# design_cty.net
KiCad netlist of a schematic drawn in Altium Designer
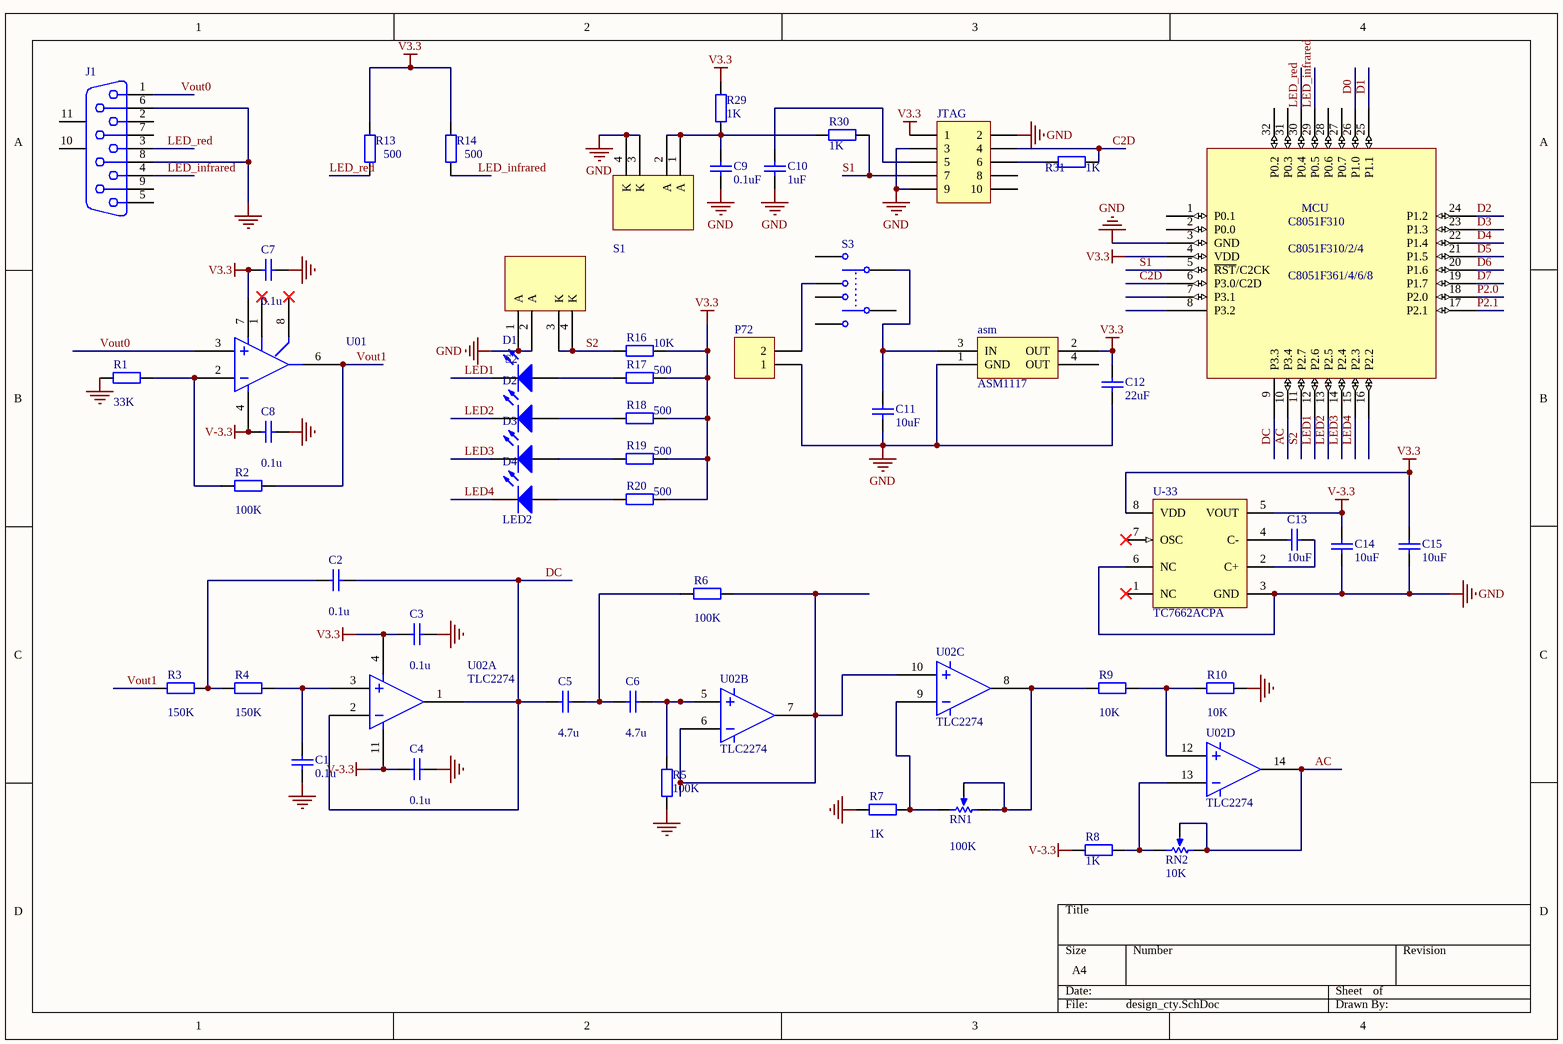
[diagram p0: design_cty.SchDoc]

(export (version "E")
  (design (tool "Eeschema 10.0.6"))
  (components
    (comp (ref "asm")
      (value "ASM1117")
      (footprint "SOT-223")
      (description "3.3V稳压芯片")
      (libsource (lib "fszhang") (part "ASM1117"))
    )
    (comp (ref "C1")
      (value "0.1u")
      (footprint "0805")
      (description "Capacitor")
      (fields (field (name "Comment") "Cap") (field (name "PUBLISHER") "Altium Limited"))
      (libsource (lib "Miscellaneous Devices") (part "Cap"))
    )
    (comp (ref "C2")
      (value "0.1u")
      (footprint "0805")
      (description "Capacitor")
      (fields (field (name "Comment") "Cap") (field (name "PUBLISHER") "Altium Limited"))
      (libsource (lib "Miscellaneous Devices") (part "Cap"))
    )
    (comp (ref "C3")
      (value "0.1u")
      (footprint "0805")
      (description "Capacitor")
      (fields (field (name "Comment") "Cap") (field (name "PUBLISHER") "Altium Limited"))
      (libsource (lib "Miscellaneous Devices") (part "Cap"))
    )
    (comp (ref "C4")
      (value "0.1u")
      (footprint "0805")
      (description "Capacitor")
      (fields (field (name "Comment") "Cap") (field (name "PUBLISHER") "Altium Limited"))
      (libsource (lib "Miscellaneous Devices") (part "Cap"))
    )
    (comp (ref "C5")
      (value "4.7u")
      (footprint "0805")
      (description "Capacitor")
      (fields (field (name "Comment") "Cap") (field (name "PUBLISHER") "Altium Limited"))
      (libsource (lib "Miscellaneous Devices") (part "Cap"))
    )
    (comp (ref "C6")
      (value "4.7u")
      (footprint "0805")
      (description "Capacitor")
      (fields (field (name "Comment") "Cap") (field (name "PUBLISHER") "Altium Limited"))
      (libsource (lib "Miscellaneous Devices") (part "Cap"))
    )
    (comp (ref "C7")
      (value "0.1u")
      (footprint "0805")
      (description "Capacitor")
      (fields (field (name "Comment") "Cap") (field (name "PUBLISHER") "Altium Limited"))
      (libsource (lib "Miscellaneous Devices") (part "Cap"))
    )
    (comp (ref "C8")
      (value "0.1u")
      (footprint "0805")
      (description "Capacitor")
      (fields (field (name "Comment") "Cap") (field (name "PUBLISHER") "Altium Limited"))
      (libsource (lib "Miscellaneous Devices") (part "Cap"))
    )
    (comp (ref "C9")
      (value "0.1uF")
      (footprint "0805")
      (description "Capacitor")
      (fields (field (name "Comment") "Cap") (field (name "PUBLISHER") "Altium Limited"))
      (libsource (lib "Miscellaneous Devices") (part "Cap"))
    )
    (comp (ref "C10")
      (value "1uF")
      (footprint "0805")
      (description "Capacitor")
      (fields (field (name "Comment") "Cap") (field (name "PUBLISHER") "Altium Limited"))
      (libsource (lib "Miscellaneous Devices") (part "Cap"))
    )
    (comp (ref "C11")
      (value "10uF")
      (footprint "1206")
      (description "Capacitor")
      (fields (field (name "Comment") "Cap") (field (name "PUBLISHER") "Altium Limited"))
      (libsource (lib "Miscellaneous Devices") (part "Cap"))
    )
    (comp (ref "C12")
      (value "22uF")
      (footprint "1206")
      (description "Capacitor")
      (fields (field (name "Comment") "Cap") (field (name "PUBLISHER") "Altium Limited"))
      (libsource (lib "Miscellaneous Devices") (part "Cap"))
    )
    (comp (ref "C13")
      (value "10uF")
      (footprint "1206")
      (description "Capacitor")
      (fields (field (name "Comment") "Cap") (field (name "PUBLISHER") "Altium Limited"))
      (libsource (lib "Miscellaneous Devices") (part "Cap"))
    )
    (comp (ref "C14")
      (value "10uF")
      (footprint "1206")
      (description "Capacitor")
      (fields (field (name "Comment") "Cap") (field (name "PUBLISHER") "Altium Limited"))
      (libsource (lib "Miscellaneous Devices") (part "Cap"))
    )
    (comp (ref "C15")
      (value "10uF")
      (footprint "1206")
      (description "Capacitor")
      (fields (field (name "Comment") "Cap") (field (name "PUBLISHER") "Altium Limited"))
      (libsource (lib "Miscellaneous Devices") (part "Cap"))
    )
    (comp (ref "D1")
      (value "LED2")
      (footprint "0805")
      (description "Typical RED, GREEN, YELLOW, AMBER GaAs LED")
      (fields (field (name "PUBLISHER") "Altium Limited"))
      (libsource (lib "Miscellaneous Devices") (part "LED2"))
    )
    (comp (ref "D2")
      (value "LED2")
      (footprint "0805")
      (description "Typical RED, GREEN, YELLOW, AMBER GaAs LED")
      (fields (field (name "PUBLISHER") "Altium Limited"))
      (libsource (lib "Miscellaneous Devices") (part "LED2"))
    )
    (comp (ref "D3")
      (value "LED2")
      (footprint "0805")
      (description "Typical RED, GREEN, YELLOW, AMBER GaAs LED")
      (fields (field (name "PUBLISHER") "Altium Limited"))
      (libsource (lib "Miscellaneous Devices") (part "LED2"))
    )
    (comp (ref "D4")
      (value "LED2")
      (footprint "0805")
      (description "Typical RED, GREEN, YELLOW, AMBER GaAs LED")
      (fields (field (name "PUBLISHER") "Altium Limited"))
      (libsource (lib "Miscellaneous Devices") (part "LED2"))
    )
    (comp (ref "J1")
      (value "D Connector 9")
      (footprint "DSUB1.385-2H9")
      (description "Receptacle Assembly, 9 Position, Right Angle")
      (fields (field (name "PUBLISHER") "Altium Limited"))
      (libsource (lib "Miscellaneous Connectors") (part "D Connector 9"))
    )
    (comp (ref "JTAG")
      (value "Header 5X2")
      (footprint "HDR2X5")
      (description "Header, 5-Pin, Dual row")
      (fields (field (name "PUBLISHER") "Altium Limited"))
      (libsource (lib "Miscellaneous Connectors") (part "Header 5X2"))
    )
    (comp (ref "MCU")
      (value "C8051F310")
      (footprint "LQFP-32")
      (libsource (lib "Siliconsch") (part "C8051F310/2/4_361/4/6/8"))
    )
    (comp (ref "P72")
      (value "Header 2")
      (footprint "HDR1X2")
      (description "Header, 2-Pin")
      (fields (field (name "PUBLISHER") "Altium Limited"))
      (libsource (lib "Miscellaneous Connectors") (part "Header 2"))
    )
    (comp (ref "R1")
      (value "33K")
      (footprint "0805")
      (description "Resistor")
      (fields (field (name "Comment") "Res2") (field (name "PUBLISHER") "Altium Limited"))
      (libsource (lib "") (part "Res2_1"))
    )
    (comp (ref "R2")
      (value "100K")
      (footprint "0805")
      (description "Resistor")
      (fields (field (name "Comment") "Res2") (field (name "PUBLISHER") "Altium Limited"))
      (libsource (lib "") (part "Res2_1"))
    )
    (comp (ref "R3")
      (value "150K")
      (footprint "0805")
      (description "Resistor")
      (fields (field (name "Comment") "Res2") (field (name "PUBLISHER") "Altium Limited"))
      (libsource (lib "") (part "Res2_1"))
    )
    (comp (ref "R4")
      (value "150K")
      (footprint "0805")
      (description "Resistor")
      (fields (field (name "Comment") "Res2") (field (name "PUBLISHER") "Altium Limited"))
      (libsource (lib "") (part "Res2_1"))
    )
    (comp (ref "R5")
      (value "100K")
      (footprint "0805")
      (description "Resistor")
      (fields (field (name "Comment") "Res2") (field (name "PUBLISHER") "Altium Limited"))
      (libsource (lib "Miscellaneous Devices") (part "Res2"))
    )
    (comp (ref "R6")
      (value "100K")
      (footprint "0805")
      (description "Resistor")
      (fields (field (name "Comment") "Res2") (field (name "PUBLISHER") "Altium Limited"))
      (libsource (lib "") (part "Res2_1"))
    )
    (comp (ref "R7")
      (value "1K")
      (footprint "0805")
      (description "Resistor")
      (fields (field (name "Comment") "Res2") (field (name "PUBLISHER") "Altium Limited"))
      (libsource (lib "") (part "Res2_1"))
    )
    (comp (ref "R8")
      (value "1K")
      (footprint "0805")
      (description "Resistor")
      (fields (field (name "Comment") "Res2") (field (name "PUBLISHER") "Altium Limited"))
      (libsource (lib "") (part "Res2_2"))
    )
    (comp (ref "R9")
      (value "10K")
      (footprint "0805")
      (description "Resistor")
      (fields (field (name "Comment") "Res2") (field (name "PUBLISHER") "Altium Limited"))
      (libsource (lib "") (part "Res2_1"))
    )
    (comp (ref "R10")
      (value "10K")
      (footprint "0805")
      (description "Resistor")
      (fields (field (name "Comment") "Res2") (field (name "PUBLISHER") "Altium Limited"))
      (libsource (lib "") (part "Res2_1"))
    )
    (comp (ref "R13")
      (value "500")
      (footprint "0805")
      (description "Resistor")
      (fields (field (name "Comment") "Res2") (field (name "PUBLISHER") "Altium Limited"))
      (libsource (lib "Miscellaneous Devices") (part "Res2"))
    )
    (comp (ref "R14")
      (value "500")
      (footprint "0805")
      (description "Resistor")
      (fields (field (name "Comment") "Res2") (field (name "PUBLISHER") "Altium Limited"))
      (libsource (lib "Miscellaneous Devices") (part "Res2"))
    )
    (comp (ref "R16")
      (value "10K")
      (footprint "0805")
      (description "Resistor")
      (fields (field (name "Comment") "Res2") (field (name "PUBLISHER") "Altium Limited"))
      (libsource (lib "") (part "Res2_1"))
    )
    (comp (ref "R17")
      (value "500")
      (footprint "0805")
      (description "Resistor")
      (fields (field (name "Comment") "Res2") (field (name "PUBLISHER") "Altium Limited"))
      (libsource (lib "") (part "Res2_1"))
    )
    (comp (ref "R18")
      (value "500")
      (footprint "0805")
      (description "Resistor")
      (fields (field (name "Comment") "Res2") (field (name "PUBLISHER") "Altium Limited"))
      (libsource (lib "") (part "Res2_1"))
    )
    (comp (ref "R19")
      (value "500")
      (footprint "0805")
      (description "Resistor")
      (fields (field (name "Comment") "Res2") (field (name "PUBLISHER") "Altium Limited"))
      (libsource (lib "") (part "Res2_1"))
    )
    (comp (ref "R20")
      (value "500")
      (footprint "0805")
      (description "Resistor")
      (fields (field (name "Comment") "Res2") (field (name "PUBLISHER") "Altium Limited"))
      (libsource (lib "") (part "Res2_1"))
    )
    (comp (ref "R29")
      (value "1K")
      (footprint "0805")
      (description "Resistor")
      (fields (field (name "Comment") "Res2") (field (name "PUBLISHER") "Altium Limited"))
      (libsource (lib "Miscellaneous Devices") (part "Res2"))
    )
    (comp (ref "R30")
      (value "1K")
      (footprint "0805")
      (description "Resistor")
      (fields (field (name "Comment") "Res2") (field (name "PUBLISHER") "Altium Limited"))
      (libsource (lib "") (part "Res2_1"))
    )
    (comp (ref "R31")
      (value "1K")
      (footprint "0805")
      (description "Resistor")
      (fields (field (name "Comment") "Res2") (field (name "PUBLISHER") "Altium Limited"))
      (libsource (lib "") (part "Res2_1"))
    )
    (comp (ref "RN1")
      (value "100K")
      (footprint "VR5")
      (description "Potentiometer")
      (fields (field (name "Comment") "RPot") (field (name "PUBLISHER") "Altium Limited"))
      (libsource (lib "Miscellaneous Devices") (part "RPot"))
    )
    (comp (ref "RN2")
      (value "10K")
      (footprint "VR5")
      (description "Potentiometer")
      (fields (field (name "Comment") "RPot") (field (name "PUBLISHER") "Altium Limited"))
      (libsource (lib "Miscellaneous Devices") (part "RPot"))
    )
    (comp (ref "S1") (value "K1") (footprint "KEY1") (libsource (lib "") (part "K1_1")))
    (comp (ref "S2") (value "K1") (footprint "KEY1") (libsource (lib "2012_2") (part "K1")))
    (comp (ref "S3")
      (value "SW-DPDT")
      (footprint "DPDT-6")
      (description "Double-Pole, Double-Throw Switch")
      (fields (field (name "PUBLISHER") "Altium Limited"))
      (libsource (lib "Miscellaneous Devices") (part "SW-DPDT"))
    )
    (comp (ref "U-33")
      (value "TC7662ACPA")
      (footprint "SO-8")
      (description "Super Charge Pump DC-to-DC Voltage Converter, 12kHz, 8-Pin PDIP, Commercial Temperature")
      (fields (field (name "PUBLISHER") "Altium Limited"))
      (libsource (lib "Microchip Power Mgt Charge Pump") (part "TC7662ACPA"))
    )
    (comp (ref "U01") (value "OP-07") (footprint "DIP-8") (libsource (lib "2012_1") (part "OP-07")))
    (comp (ref "U02") (value "TLC2274") (footprint "SOP-14N") (libsource (lib "2012_1") (part "LM324")))
  )
  (nets
    (net (code "1") (name "/AC") (class "Default")
      (node (ref "MCU") (pin "10") (pinfunction "P3.4_10") (pintype "bidirectional"))
      (node (ref "RN2") (pin "1") (pinfunction "TOP_1") (pintype "passive"))
      (node (ref "RN2") (pin "3") (pinfunction "TAP_3") (pintype "passive"))
      (node (ref "U02") (pin "14") (pintype "passive"))
    )
    (net (code "2") (name "/C2D") (class "Default")
      (node (ref "JTAG") (pin "4") (pinfunction "4_4") (pintype "passive"))
      (node (ref "MCU") (pin "6") (pinfunction "P3.0/C2D_6") (pintype "bidirectional"))
      (node (ref "R31") (pin "2") (pinfunction "2_2") (pintype "passive"))
    )
    (net (code "3") (name "/D0") (class "Default")
      (node (ref "MCU") (pin "26") (pinfunction "P1.0_26") (pintype "bidirectional"))
    )
    (net (code "4") (name "/D1") (class "Default")
      (node (ref "MCU") (pin "25") (pinfunction "P1.1_25") (pintype "bidirectional"))
    )
    (net (code "5") (name "/D2") (class "Default")
      (node (ref "MCU") (pin "24") (pinfunction "P1.2_24") (pintype "bidirectional"))
    )
    (net (code "6") (name "/D3") (class "Default")
      (node (ref "MCU") (pin "23") (pinfunction "P1.3_23") (pintype "bidirectional"))
    )
    (net (code "7") (name "/D4") (class "Default")
      (node (ref "MCU") (pin "22") (pinfunction "P1.4_22") (pintype "bidirectional"))
    )
    (net (code "8") (name "/D5") (class "Default")
      (node (ref "MCU") (pin "21") (pinfunction "P1.5_21") (pintype "bidirectional"))
    )
    (net (code "9") (name "/D6") (class "Default")
      (node (ref "MCU") (pin "20") (pinfunction "P1.6_20") (pintype "bidirectional"))
    )
    (net (code "10") (name "/D7") (class "Default")
      (node (ref "MCU") (pin "19") (pinfunction "P1.7_19") (pintype "bidirectional"))
    )
    (net (code "11") (name "/DC") (class "Default")
      (node (ref "C2") (pin "2") (pinfunction "2_2") (pintype "passive"))
      (node (ref "C5") (pin "1") (pinfunction "1_1") (pintype "passive"))
      (node (ref "MCU") (pin "9") (pinfunction "P3.3_9") (pintype "power_in"))
      (node (ref "U02") (pin "1") (pintype "passive"))
      (node (ref "U02") (pin "2") (pintype "passive"))
    )
    (net (code "12") (name "/LED1") (class "Default")
      (node (ref "D1") (pin "2") (pinfunction "K_2") (pintype "passive"))
      (node (ref "MCU") (pin "12") (pinfunction "P2.6_12") (pintype "bidirectional"))
    )
    (net (code "13") (name "/LED2") (class "Default")
      (node (ref "D2") (pin "2") (pinfunction "K_2") (pintype "passive"))
      (node (ref "MCU") (pin "13") (pinfunction "P2.5_13") (pintype "bidirectional"))
    )
    (net (code "14") (name "/LED3") (class "Default")
      (node (ref "D3") (pin "2") (pinfunction "K_2") (pintype "passive"))
      (node (ref "MCU") (pin "14") (pinfunction "P2.4_14") (pintype "bidirectional"))
    )
    (net (code "15") (name "/LED4") (class "Default")
      (node (ref "D4") (pin "2") (pinfunction "K_2") (pintype "passive"))
      (node (ref "MCU") (pin "15") (pinfunction "P2.3_15") (pintype "bidirectional"))
    )
    (net (code "16") (name "/LED_infrared") (class "Default")
      (node (ref "J1") (pin "4") (pinfunction "4_4") (pintype "passive"))
      (node (ref "MCU") (pin "29") (pinfunction "P0.5_29") (pintype "bidirectional"))
      (node (ref "R14") (pin "1") (pinfunction "1_1") (pintype "passive"))
    )
    (net (code "17") (name "/LED_red") (class "Default")
      (node (ref "J1") (pin "3") (pinfunction "3_3") (pintype "passive"))
      (node (ref "MCU") (pin "30") (pinfunction "P0.4_30") (pintype "bidirectional"))
      (node (ref "R13") (pin "1") (pinfunction "1_1") (pintype "passive"))
    )
    (net (code "18") (name "/P2.0") (class "Default")
      (node (ref "MCU") (pin "18") (pinfunction "P2.0_18") (pintype "bidirectional"))
    )
    (net (code "19") (name "/P2.1") (class "Default")
      (node (ref "MCU") (pin "17") (pinfunction "P2.1_17") (pintype "bidirectional"))
    )
    (net (code "20") (name "/S1") (class "Default")
      (node (ref "JTAG") (pin "7") (pinfunction "7_7") (pintype "passive"))
      (node (ref "MCU") (pin "5") (pinfunction "~{RST}/C2CK_5") (pintype "bidirectional"))
      (node (ref "R30") (pin "2") (pinfunction "2_2") (pintype "passive"))
    )
    (net (code "21") (name "/S2") (class "Default")
      (node (ref "MCU") (pin "11") (pinfunction "P2.7_11") (pintype "bidirectional"))
      (node (ref "R16") (pin "1") (pinfunction "1_1") (pintype "passive"))
      (node (ref "S2") (pin "3") (pinfunction "K_3") (pintype "passive"))
      (node (ref "S2") (pin "4") (pinfunction "K_4") (pintype "passive"))
    )
    (net (code "22") (name "/Vout0") (class "Default")
      (node (ref "J1") (pin "1") (pinfunction "1_1") (pintype "passive"))
      (node (ref "U01") (pin "3") (pintype "passive"))
    )
    (net (code "23") (name "/Vout1") (class "Default")
      (node (ref "R2") (pin "2") (pinfunction "2_2") (pintype "passive"))
      (node (ref "R3") (pin "1") (pinfunction "1_1") (pintype "passive"))
      (node (ref "U01") (pin "6") (pintype "passive"))
    )
    (net (code "24") (name "GND") (class "Default")
      (node (ref "C1") (pin "1") (pinfunction "1_1") (pintype "passive"))
      (node (ref "C10") (pin "1") (pinfunction "1_1") (pintype "passive"))
      (node (ref "C11") (pin "1") (pinfunction "1_1") (pintype "passive"))
      (node (ref "C12") (pin "1") (pinfunction "1_1") (pintype "passive"))
      (node (ref "C14") (pin "1") (pinfunction "1_1") (pintype "passive"))
      (node (ref "C15") (pin "1") (pinfunction "1_1") (pintype "passive"))
      (node (ref "C3") (pin "2") (pinfunction "2_2") (pintype "passive"))
      (node (ref "C4") (pin "2") (pinfunction "2_2") (pintype "passive"))
      (node (ref "C7") (pin "2") (pinfunction "2_2") (pintype "passive"))
      (node (ref "C8") (pin "2") (pinfunction "2_2") (pintype "passive"))
      (node (ref "C9") (pin "1") (pinfunction "1_1") (pintype "passive"))
      (node (ref "J1") (pin "6") (pinfunction "6_6") (pintype "passive"))
      (node (ref "J1") (pin "8") (pinfunction "8_8") (pintype "passive"))
      (node (ref "JTAG") (pin "2") (pinfunction "2_2") (pintype "passive"))
      (node (ref "JTAG") (pin "3") (pinfunction "3_3") (pintype "passive"))
      (node (ref "JTAG") (pin "9") (pinfunction "9_9") (pintype "passive"))
      (node (ref "MCU") (pin "3") (pinfunction "GND_3") (pintype "bidirectional"))
      (node (ref "P72") (pin "1") (pinfunction "1_1") (pintype "passive"))
      (node (ref "R1") (pin "1") (pinfunction "1_1") (pintype "passive"))
      (node (ref "R10") (pin "2") (pinfunction "2_2") (pintype "passive"))
      (node (ref "R5") (pin "1") (pinfunction "1_1") (pintype "passive"))
      (node (ref "R7") (pin "1") (pinfunction "1_1") (pintype "passive"))
      (node (ref "S1") (pin "3") (pinfunction "K_3") (pintype "passive"))
      (node (ref "S1") (pin "4") (pinfunction "K_4") (pintype "passive"))
      (node (ref "S2") (pin "1") (pinfunction "A_1") (pintype "passive"))
      (node (ref "S2") (pin "2") (pinfunction "A_2") (pintype "passive"))
      (node (ref "U-33") (pin "3") (pinfunction "GND_3") (pintype "power_in"))
      (node (ref "U-33") (pin "6") (pinfunction "NC_6") (pintype "passive"))
      (node (ref "asm") (pin "1") (pinfunction "GND_1") (pintype "passive"))
    )
    (net (code "25") (name "Net-(C1-Pad2)") (class "Default")
      (node (ref "C1") (pin "2") (pinfunction "2_2") (pintype "passive"))
      (node (ref "R4") (pin "2") (pinfunction "2_2") (pintype "passive"))
      (node (ref "U02") (pin "3") (pintype "passive"))
    )
    (net (code "26") (name "Net-(C2-Pad1)") (class "Default")
      (node (ref "C2") (pin "1") (pinfunction "1_1") (pintype "passive"))
      (node (ref "R3") (pin "2") (pinfunction "2_2") (pintype "passive"))
      (node (ref "R4") (pin "1") (pinfunction "1_1") (pintype "passive"))
    )
    (net (code "27") (name "Net-(C5-Pad2)") (class "Default")
      (node (ref "C5") (pin "2") (pinfunction "2_2") (pintype "passive"))
      (node (ref "C6") (pin "1") (pinfunction "1_1") (pintype "passive"))
      (node (ref "R6") (pin "1") (pinfunction "1_1") (pintype "passive"))
    )
    (net (code "28") (name "Net-(C6-Pad2)") (class "Default")
      (node (ref "C6") (pin "2") (pinfunction "2_2") (pintype "passive"))
      (node (ref "R5") (pin "2") (pinfunction "2_2") (pintype "passive"))
      (node (ref "U02") (pin "5") (pintype "passive"))
    )
    (net (code "29") (name "Net-(C9-Pad2)") (class "Default")
      (node (ref "C9") (pin "2") (pinfunction "2_2") (pintype "passive"))
      (node (ref "R29") (pin "1") (pinfunction "1_1") (pintype "passive"))
      (node (ref "R30") (pin "1") (pinfunction "1_1") (pintype "passive"))
      (node (ref "S1") (pin "1") (pinfunction "A_1") (pintype "passive"))
      (node (ref "S1") (pin "2") (pinfunction "A_2") (pintype "passive"))
    )
    (net (code "30") (name "Net-(C10-Pad2)") (class "Default")
      (node (ref "C10") (pin "2") (pinfunction "2_2") (pintype "passive"))
      (node (ref "JTAG") (pin "5") (pinfunction "5_5") (pintype "passive"))
    )
    (net (code "31") (name "Net-(D1-A)") (class "Default")
      (node (ref "D1") (pin "1") (pinfunction "A_1") (pintype "passive"))
      (node (ref "R17") (pin "1") (pinfunction "1_1") (pintype "passive"))
    )
    (net (code "32") (name "Net-(D2-A)") (class "Default")
      (node (ref "D2") (pin "1") (pinfunction "A_1") (pintype "passive"))
      (node (ref "R18") (pin "1") (pinfunction "1_1") (pintype "passive"))
    )
    (net (code "33") (name "Net-(D3-A)") (class "Default")
      (node (ref "D3") (pin "1") (pinfunction "A_1") (pintype "passive"))
      (node (ref "R19") (pin "1") (pinfunction "1_1") (pintype "passive"))
    )
    (net (code "34") (name "Net-(D4-A)") (class "Default")
      (node (ref "D4") (pin "1") (pinfunction "A_1") (pintype "passive"))
      (node (ref "R20") (pin "1") (pinfunction "1_1") (pintype "passive"))
    )
    (net (code "35") (name "Net-(JTAG-Pad6)") (class "Default")
      (node (ref "JTAG") (pin "6") (pinfunction "6_6") (pintype "passive"))
      (node (ref "R31") (pin "1") (pinfunction "1_1") (pintype "passive"))
    )
    (net (code "36") (name "Net-(P72-Pad2)") (class "Default")
      (node (ref "P72") (pin "2") (pinfunction "2_2") (pintype "passive"))
      (node (ref "S3") (pin "5") (pinfunction "5_5") (pintype "passive"))
    )
    (net (code "37") (name "Net-(R1-Pad2)") (class "Default")
      (node (ref "R1") (pin "2") (pinfunction "2_2") (pintype "passive"))
      (node (ref "R2") (pin "1") (pinfunction "1_1") (pintype "passive"))
      (node (ref "U01") (pin "2") (pintype "passive"))
    )
    (net (code "38") (name "Net-(R6-Pad2)") (class "Default")
      (node (ref "R6") (pin "2") (pinfunction "2_2") (pintype "passive"))
      (node (ref "U02") (pin "10") (pintype "passive"))
      (node (ref "U02") (pin "6") (pintype "passive"))
      (node (ref "U02") (pin "7") (pintype "passive"))
    )
    (net (code "39") (name "Net-(R10-Pad1)") (class "Default")
      (node (ref "R10") (pin "1") (pinfunction "1_1") (pintype "passive"))
      (node (ref "R9") (pin "2") (pinfunction "2_2") (pintype "passive"))
      (node (ref "U02") (pin "12") (pintype "passive"))
    )
    (net (code "40") (name "Net-(RN1-BOT)") (class "Default")
      (node (ref "R7") (pin "2") (pinfunction "2_2") (pintype "passive"))
      (node (ref "RN1") (pin "2") (pinfunction "BOT_2") (pintype "passive"))
      (node (ref "U02") (pin "9") (pintype "passive"))
    )
    (net (code "41") (name "Net-(RN1-TAP)") (class "Default")
      (node (ref "R9") (pin "1") (pinfunction "1_1") (pintype "passive"))
      (node (ref "RN1") (pin "1") (pinfunction "TOP_1") (pintype "passive"))
      (node (ref "RN1") (pin "3") (pinfunction "TAP_3") (pintype "passive"))
      (node (ref "U02") (pin "8") (pintype "passive"))
    )
    (net (code "42") (name "Net-(RN2-BOT)") (class "Default")
      (node (ref "R8") (pin "1") (pinfunction "1_1") (pintype "passive"))
      (node (ref "RN2") (pin "2") (pinfunction "BOT_2") (pintype "passive"))
      (node (ref "U02") (pin "13") (pintype "passive"))
    )
    (net (code "43") (name "Net-(U-33-C+)") (class "Default")
      (node (ref "C13") (pin "1") (pinfunction "1_1") (pintype "passive"))
      (node (ref "U-33") (pin "2") (pinfunction "C+_2") (pintype "passive"))
    )
    (net (code "44") (name "Net-(U-33-C-)") (class "Default")
      (node (ref "C13") (pin "2") (pinfunction "2_2") (pintype "passive"))
      (node (ref "U-33") (pin "4") (pinfunction "C-_4") (pintype "passive"))
    )
    (net (code "45") (name "Net-(asm-IN)") (class "Default")
      (node (ref "C11") (pin "2") (pinfunction "2_2") (pintype "passive"))
      (node (ref "S3") (pin "4") (pinfunction "4_4") (pintype "passive"))
      (node (ref "asm") (pin "3") (pinfunction "IN_3") (pintype "passive"))
    )
    (net (code "46") (name "V-3.3") (class "Default")
      (node (ref "C14") (pin "2") (pinfunction "2_2") (pintype "passive"))
      (node (ref "C4") (pin "1") (pinfunction "1_1") (pintype "passive"))
      (node (ref "C8") (pin "1") (pinfunction "1_1") (pintype "passive"))
      (node (ref "R8") (pin "2") (pinfunction "2_2") (pintype "passive"))
      (node (ref "U-33") (pin "5") (pinfunction "VOUT_5") (pintype "power_in"))
      (node (ref "U01") (pin "4") (pintype "passive"))
      (node (ref "U02") (pin "11") (pintype "passive"))
    )
    (net (code "47") (name "V3.3") (class "Default")
      (node (ref "C12") (pin "2") (pinfunction "2_2") (pintype "passive"))
      (node (ref "C15") (pin "2") (pinfunction "2_2") (pintype "passive"))
      (node (ref "C3") (pin "1") (pinfunction "1_1") (pintype "passive"))
      (node (ref "C7") (pin "1") (pinfunction "1_1") (pintype "passive"))
      (node (ref "JTAG") (pin "1") (pinfunction "1_1") (pintype "passive"))
      (node (ref "MCU") (pin "4") (pinfunction "VDD_4") (pintype "bidirectional"))
      (node (ref "R13") (pin "2") (pinfunction "2_2") (pintype "passive"))
      (node (ref "R14") (pin "2") (pinfunction "2_2") (pintype "passive"))
      (node (ref "R16") (pin "2") (pinfunction "2_2") (pintype "passive"))
      (node (ref "R17") (pin "2") (pinfunction "2_2") (pintype "passive"))
      (node (ref "R18") (pin "2") (pinfunction "2_2") (pintype "passive"))
      (node (ref "R19") (pin "2") (pinfunction "2_2") (pintype "passive"))
      (node (ref "R20") (pin "2") (pinfunction "2_2") (pintype "passive"))
      (node (ref "R29") (pin "2") (pinfunction "2_2") (pintype "passive"))
      (node (ref "U-33") (pin "8") (pinfunction "VDD_8") (pintype "power_in"))
      (node (ref "U01") (pin "7") (pintype "passive"))
      (node (ref "U02") (pin "4") (pintype "passive"))
      (node (ref "asm") (pin "2") (pinfunction "OUT_2") (pintype "passive"))
    )
    (net (code "48") (name "unconnected-(J1-MH1-Pad10)") (class "Default")
      (node (ref "J1") (pin "10") (pinfunction "MH1_10") (pintype "passive"))
    )
    (net (code "49") (name "unconnected-(J1-MH2-Pad11)") (class "Default")
      (node (ref "J1") (pin "11") (pinfunction "MH2_11") (pintype "passive"))
    )
    (net (code "50") (name "unconnected-(J1-Pad2)") (class "Default")
      (node (ref "J1") (pin "2") (pinfunction "2_2") (pintype "passive"))
    )
    (net (code "51") (name "unconnected-(J1-Pad5)") (class "Default")
      (node (ref "J1") (pin "5") (pinfunction "5_5") (pintype "passive"))
    )
    (net (code "52") (name "unconnected-(J1-Pad7)") (class "Default")
      (node (ref "J1") (pin "7") (pinfunction "7_7") (pintype "passive"))
    )
    (net (code "53") (name "unconnected-(J1-Pad9)") (class "Default")
      (node (ref "J1") (pin "9") (pinfunction "9_9") (pintype "passive"))
    )
    (net (code "54") (name "unconnected-(JTAG-Pad8)") (class "Default")
      (node (ref "JTAG") (pin "8") (pinfunction "8_8") (pintype "passive"))
    )
    (net (code "55") (name "unconnected-(JTAG-Pad10)") (class "Default")
      (node (ref "JTAG") (pin "10") (pinfunction "10_10") (pintype "passive"))
    )
    (net (code "56") (name "unconnected-(MCU-P0.0-Pad2)") (class "Default")
      (node (ref "MCU") (pin "2") (pinfunction "P0.0_2") (pintype "bidirectional"))
    )
    (net (code "57") (name "unconnected-(MCU-P0.1-Pad1)") (class "Default")
      (node (ref "MCU") (pin "1") (pinfunction "P0.1_1") (pintype "bidirectional"))
    )
    (net (code "58") (name "unconnected-(MCU-P0.2-Pad32)") (class "Default")
      (node (ref "MCU") (pin "32") (pinfunction "P0.2_32") (pintype "bidirectional"))
    )
    (net (code "59") (name "unconnected-(MCU-P0.3-Pad31)") (class "Default")
      (node (ref "MCU") (pin "31") (pinfunction "P0.3_31") (pintype "bidirectional"))
    )
    (net (code "60") (name "unconnected-(MCU-P0.6-Pad28)") (class "Default")
      (node (ref "MCU") (pin "28") (pinfunction "P0.6_28") (pintype "bidirectional"))
    )
    (net (code "61") (name "unconnected-(MCU-P0.7-Pad27)") (class "Default")
      (node (ref "MCU") (pin "27") (pinfunction "P0.7_27") (pintype "bidirectional"))
    )
    (net (code "62") (name "unconnected-(MCU-P2.2-Pad16)") (class "Default")
      (node (ref "MCU") (pin "16") (pinfunction "P2.2_16") (pintype "bidirectional"))
    )
    (net (code "63") (name "unconnected-(MCU-P3.1-Pad7)") (class "Default")
      (node (ref "MCU") (pin "7") (pinfunction "P3.1_7") (pintype "bidirectional"))
    )
    (net (code "64") (name "unconnected-(MCU-P3.2-Pad8)") (class "Default")
      (node (ref "MCU") (pin "8") (pinfunction "P3.2_8") (pintype "power_in"))
    )
    (net (code "65") (name "unconnected-(S3-Pad1)") (class "Default")
      (node (ref "S3") (pin "1") (pinfunction "1_1") (pintype "passive"))
    )
    (net (code "66") (name "unconnected-(S3-Pad2)") (class "Default")
      (node (ref "S3") (pin "2") (pinfunction "2_2") (pintype "passive"))
    )
    (net (code "67") (name "unconnected-(S3-Pad3)") (class "Default")
      (node (ref "S3") (pin "3") (pinfunction "3_3") (pintype "passive"))
    )
    (net (code "68") (name "unconnected-(S3-Pad6)") (class "Default")
      (node (ref "S3") (pin "6") (pinfunction "6_6") (pintype "passive"))
    )
    (net (code "69") (name "unconnected-(U-33-NC-Pad1)") (class "Default")
      (node (ref "U-33") (pin "1") (pinfunction "NC_1") (pintype "passive+no_connect"))
    )
    (net (code "70") (name "unconnected-(U-33-OSC-Pad7)") (class "Default")
      (node (ref "U-33") (pin "7") (pinfunction "OSC_7") (pintype "input+no_connect"))
    )
    (net (code "71") (name "unconnected-(U01-Pad1)") (class "Default")
      (node (ref "U01") (pin "1") (pintype "passive+no_connect"))
    )
    (net (code "72") (name "unconnected-(U01-Pad8)") (class "Default")
      (node (ref "U01") (pin "8") (pintype "passive+no_connect"))
    )
    (net (code "73") (name "unconnected-(asm-OUT-Pad4)") (class "Default")
      (node (ref "asm") (pin "4") (pinfunction "OUT_4") (pintype "passive"))
    )
  )
)
